# PulseSensor.net
KiCad netlist of a schematic drawn in EAGLE
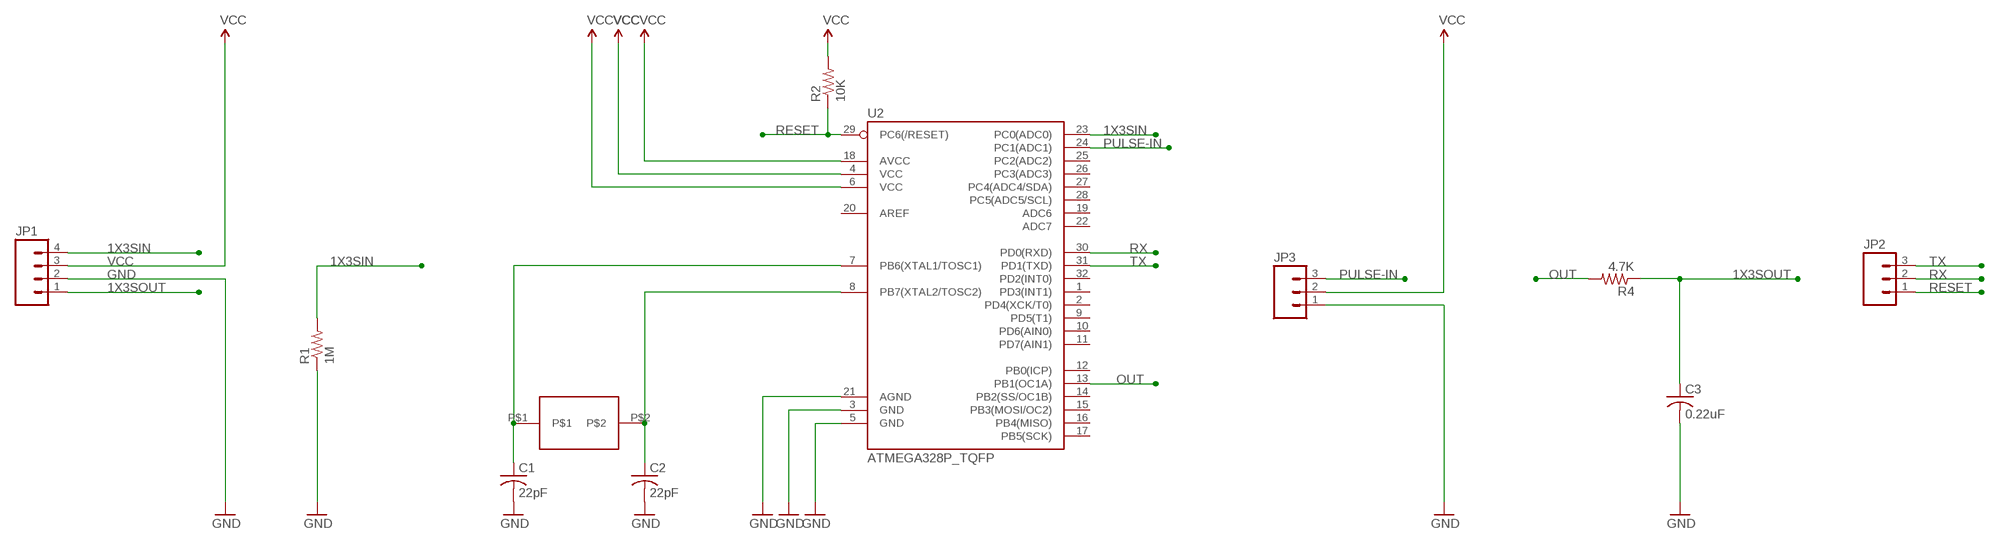
[diagram p0: schematic, sheet 1]

(export (version "E")
  (design (tool "Eeschema 10.0.6"))
  (components
    (comp (ref "C1")
      (value "22pF")
      (footprint "eagle-import:C0603")
      (libsource (lib "eagle-import") (part "C-USC0603"))
    )
    (comp (ref "C2")
      (value "22pF")
      (footprint "eagle-import:C0603")
      (libsource (lib "eagle-import") (part "C-USC0603"))
    )
    (comp (ref "C3")
      (value "0.22uF")
      (footprint "eagle-import:C0603")
      (libsource (lib "eagle-import") (part "C-USC0603"))
    )
    (comp (ref "JP1")
      (value "M04PTH")
      (footprint "eagle-import:1X04")
      (libsource (lib "eagle-import") (part "M04PTH"))
    )
    (comp (ref "JP2")
      (value "M03PTH")
      (footprint "eagle-import:1X03")
      (libsource (lib "eagle-import") (part "M03PTH"))
    )
    (comp (ref "JP3")
      (value "M031X03_NO_HOLES")
      (footprint "eagle-import:1X03_NO_HOLES")
      (libsource (lib "eagle-import") (part "M031X03_NO_HOLES"))
    )
    (comp (ref "R1")
      (value "1M")
      (footprint "eagle-import:R0603")
      (libsource (lib "eagle-import") (part "R-US_R0603"))
    )
    (comp (ref "R2")
      (value "10K")
      (footprint "eagle-import:R0603")
      (libsource (lib "eagle-import") (part "resistor_R-US_R0603"))
    )
    (comp (ref "R4")
      (value "4.7K")
      (footprint "eagle-import:R0603")
      (libsource (lib "eagle-import") (part "R-US_R0603"))
    )
    (comp (ref "U$2")
      (value "NX503")
      (footprint "eagle-import:NX503")
      (libsource (lib "eagle-import") (part "NX503"))
    )
    (comp (ref "U2")
      (value "ATMEGA328P_TQFP")
      (footprint "eagle-import:TQFP32-08")
      (libsource (lib "eagle-import") (part "ATMEGA328P_TQFP"))
    )
  )
  (nets
    (net (code "1") (name "/1X3SIN") (class "Default")
      (node (ref "JP1") (pin "4") (pinfunction "4_4") (pintype "passive"))
      (node (ref "R1") (pin "2") (pinfunction "2_2") (pintype "passive"))
      (node (ref "U2") (pin "23") (pinfunction "PC0(ADC0)_23") (pintype "bidirectional"))
    )
    (net (code "2") (name "/1X3SOUT") (class "Default")
      (node (ref "C3") (pin "1") (pinfunction "1_1") (pintype "passive"))
      (node (ref "JP1") (pin "1") (pinfunction "1_1") (pintype "passive"))
      (node (ref "R4") (pin "1") (pinfunction "1_1") (pintype "passive"))
    )
    (net (code "3") (name "/OUT") (class "Default")
      (node (ref "R4") (pin "2") (pinfunction "2_2") (pintype "passive"))
      (node (ref "U2") (pin "13") (pinfunction "PB1(OC1A)_13") (pintype "bidirectional"))
    )
    (net (code "4") (name "/PULSE-IN") (class "Default")
      (node (ref "JP3") (pin "3") (pinfunction "3_3") (pintype "passive"))
      (node (ref "U2") (pin "24") (pinfunction "PC1(ADC1)_24") (pintype "bidirectional"))
    )
    (net (code "5") (name "/RESET") (class "Default")
      (node (ref "JP2") (pin "1") (pinfunction "1_1") (pintype "passive"))
      (node (ref "R2") (pin "1") (pinfunction "1_1") (pintype "passive"))
      (node (ref "U2") (pin "29") (pinfunction "PC6(/RESET)_29") (pintype "bidirectional"))
    )
    (net (code "6") (name "/RX") (class "Default")
      (node (ref "JP2") (pin "2") (pinfunction "2_2") (pintype "passive"))
      (node (ref "U2") (pin "30") (pinfunction "PD0(RXD)_30") (pintype "bidirectional"))
    )
    (net (code "7") (name "/TX") (class "Default")
      (node (ref "JP2") (pin "3") (pinfunction "3_3") (pintype "passive"))
      (node (ref "U2") (pin "31") (pinfunction "PD1(TXD)_31") (pintype "bidirectional"))
    )
    (net (code "8") (name "GND") (class "Default")
      (node (ref "C1") (pin "2") (pinfunction "2_2") (pintype "passive"))
      (node (ref "C2") (pin "2") (pinfunction "2_2") (pintype "passive"))
      (node (ref "C3") (pin "2") (pinfunction "2_2") (pintype "passive"))
      (node (ref "JP1") (pin "2") (pinfunction "2_2") (pintype "passive"))
      (node (ref "JP3") (pin "1") (pinfunction "1_1") (pintype "passive"))
      (node (ref "R1") (pin "1") (pinfunction "1_1") (pintype "passive"))
      (node (ref "U2") (pin "21") (pinfunction "AGND_21") (pintype "bidirectional"))
      (node (ref "U2") (pin "3") (pinfunction "GND_3") (pintype "bidirectional"))
      (node (ref "U2") (pin "5") (pinfunction "GND_5") (pintype "bidirectional"))
    )
    (net (code "9") (name "Net-(U2-PB6(XTAL1{slash}TOSC1))") (class "Default")
      (node (ref "C1") (pin "1") (pinfunction "1_1") (pintype "passive"))
      (node (ref "U$2") (pin "P$1") (pinfunction "P$1_P$1") (pintype "bidirectional"))
      (node (ref "U2") (pin "7") (pinfunction "PB6(XTAL1/TOSC1)_7") (pintype "bidirectional"))
    )
    (net (code "10") (name "Net-(U2-PB7(XTAL2{slash}TOSC2))") (class "Default")
      (node (ref "C2") (pin "1") (pinfunction "1_1") (pintype "passive"))
      (node (ref "U$2") (pin "P$2") (pinfunction "P$2_P$2") (pintype "bidirectional"))
      (node (ref "U2") (pin "8") (pinfunction "PB7(XTAL2/TOSC2)_8") (pintype "bidirectional"))
    )
    (net (code "11") (name "VCC") (class "Default")
      (node (ref "JP1") (pin "3") (pinfunction "3_3") (pintype "passive"))
      (node (ref "JP3") (pin "2") (pinfunction "2_2") (pintype "passive"))
      (node (ref "R2") (pin "2") (pinfunction "2_2") (pintype "passive"))
      (node (ref "U2") (pin "18") (pinfunction "AVCC_18") (pintype "bidirectional"))
      (node (ref "U2") (pin "4") (pinfunction "VCC_4") (pintype "bidirectional"))
      (node (ref "U2") (pin "6") (pinfunction "VCC_6") (pintype "bidirectional"))
    )
    (net (code "12") (name "unconnected-(U2-ADC6-Pad19)") (class "Default")
      (node (ref "U2") (pin "19") (pinfunction "ADC6_19") (pintype "bidirectional"))
    )
    (net (code "13") (name "unconnected-(U2-ADC7-Pad22)") (class "Default")
      (node (ref "U2") (pin "22") (pinfunction "ADC7_22") (pintype "bidirectional"))
    )
    (net (code "14") (name "unconnected-(U2-AREF-Pad20)") (class "Default")
      (node (ref "U2") (pin "20") (pinfunction "AREF_20") (pintype "bidirectional"))
    )
    (net (code "15") (name "unconnected-(U2-PB0(ICP)-Pad12)") (class "Default")
      (node (ref "U2") (pin "12") (pinfunction "PB0(ICP)_12") (pintype "bidirectional"))
    )
    (net (code "16") (name "unconnected-(U2-PB2(SS{slash}OC1B)-Pad14)") (class "Default")
      (node (ref "U2") (pin "14") (pinfunction "PB2(SS/OC1B)_14") (pintype "bidirectional"))
    )
    (net (code "17") (name "unconnected-(U2-PB3(MOSI{slash}OC2)-Pad15)") (class "Default")
      (node (ref "U2") (pin "15") (pinfunction "PB3(MOSI/OC2)_15") (pintype "bidirectional"))
    )
    (net (code "18") (name "unconnected-(U2-PB4(MISO)-Pad16)") (class "Default")
      (node (ref "U2") (pin "16") (pinfunction "PB4(MISO)_16") (pintype "bidirectional"))
    )
    (net (code "19") (name "unconnected-(U2-PB5(SCK)-Pad17)") (class "Default")
      (node (ref "U2") (pin "17") (pinfunction "PB5(SCK)_17") (pintype "bidirectional"))
    )
    (net (code "20") (name "unconnected-(U2-PC2(ADC2)-Pad25)") (class "Default")
      (node (ref "U2") (pin "25") (pinfunction "PC2(ADC2)_25") (pintype "bidirectional"))
    )
    (net (code "21") (name "unconnected-(U2-PC3(ADC3)-Pad26)") (class "Default")
      (node (ref "U2") (pin "26") (pinfunction "PC3(ADC3)_26") (pintype "bidirectional"))
    )
    (net (code "22") (name "unconnected-(U2-PC4(ADC4{slash}SDA)-Pad27)") (class "Default")
      (node (ref "U2") (pin "27") (pinfunction "PC4(ADC4/SDA)_27") (pintype "bidirectional"))
    )
    (net (code "23") (name "unconnected-(U2-PC5(ADC5{slash}SCL)-Pad28)") (class "Default")
      (node (ref "U2") (pin "28") (pinfunction "PC5(ADC5/SCL)_28") (pintype "bidirectional"))
    )
    (net (code "24") (name "unconnected-(U2-PD2(INT0)-Pad32)") (class "Default")
      (node (ref "U2") (pin "32") (pinfunction "PD2(INT0)_32") (pintype "bidirectional"))
    )
    (net (code "25") (name "unconnected-(U2-PD3(INT1)-Pad1)") (class "Default")
      (node (ref "U2") (pin "1") (pinfunction "PD3(INT1)_1") (pintype "bidirectional"))
    )
    (net (code "26") (name "unconnected-(U2-PD4(XCK{slash}T0)-Pad2)") (class "Default")
      (node (ref "U2") (pin "2") (pinfunction "PD4(XCK/T0)_2") (pintype "bidirectional"))
    )
    (net (code "27") (name "unconnected-(U2-PD5(T1)-Pad9)") (class "Default")
      (node (ref "U2") (pin "9") (pinfunction "PD5(T1)_9") (pintype "bidirectional"))
    )
    (net (code "28") (name "unconnected-(U2-PD6(AIN0)-Pad10)") (class "Default")
      (node (ref "U2") (pin "10") (pinfunction "PD6(AIN0)_10") (pintype "bidirectional"))
    )
    (net (code "29") (name "unconnected-(U2-PD7(AIN1)-Pad11)") (class "Default")
      (node (ref "U2") (pin "11") (pinfunction "PD7(AIN1)_11") (pintype "bidirectional"))
    )
  )
)
